# OSSILEDControllerNew.net
KiCad netlist of a schematic drawn in EAGLE
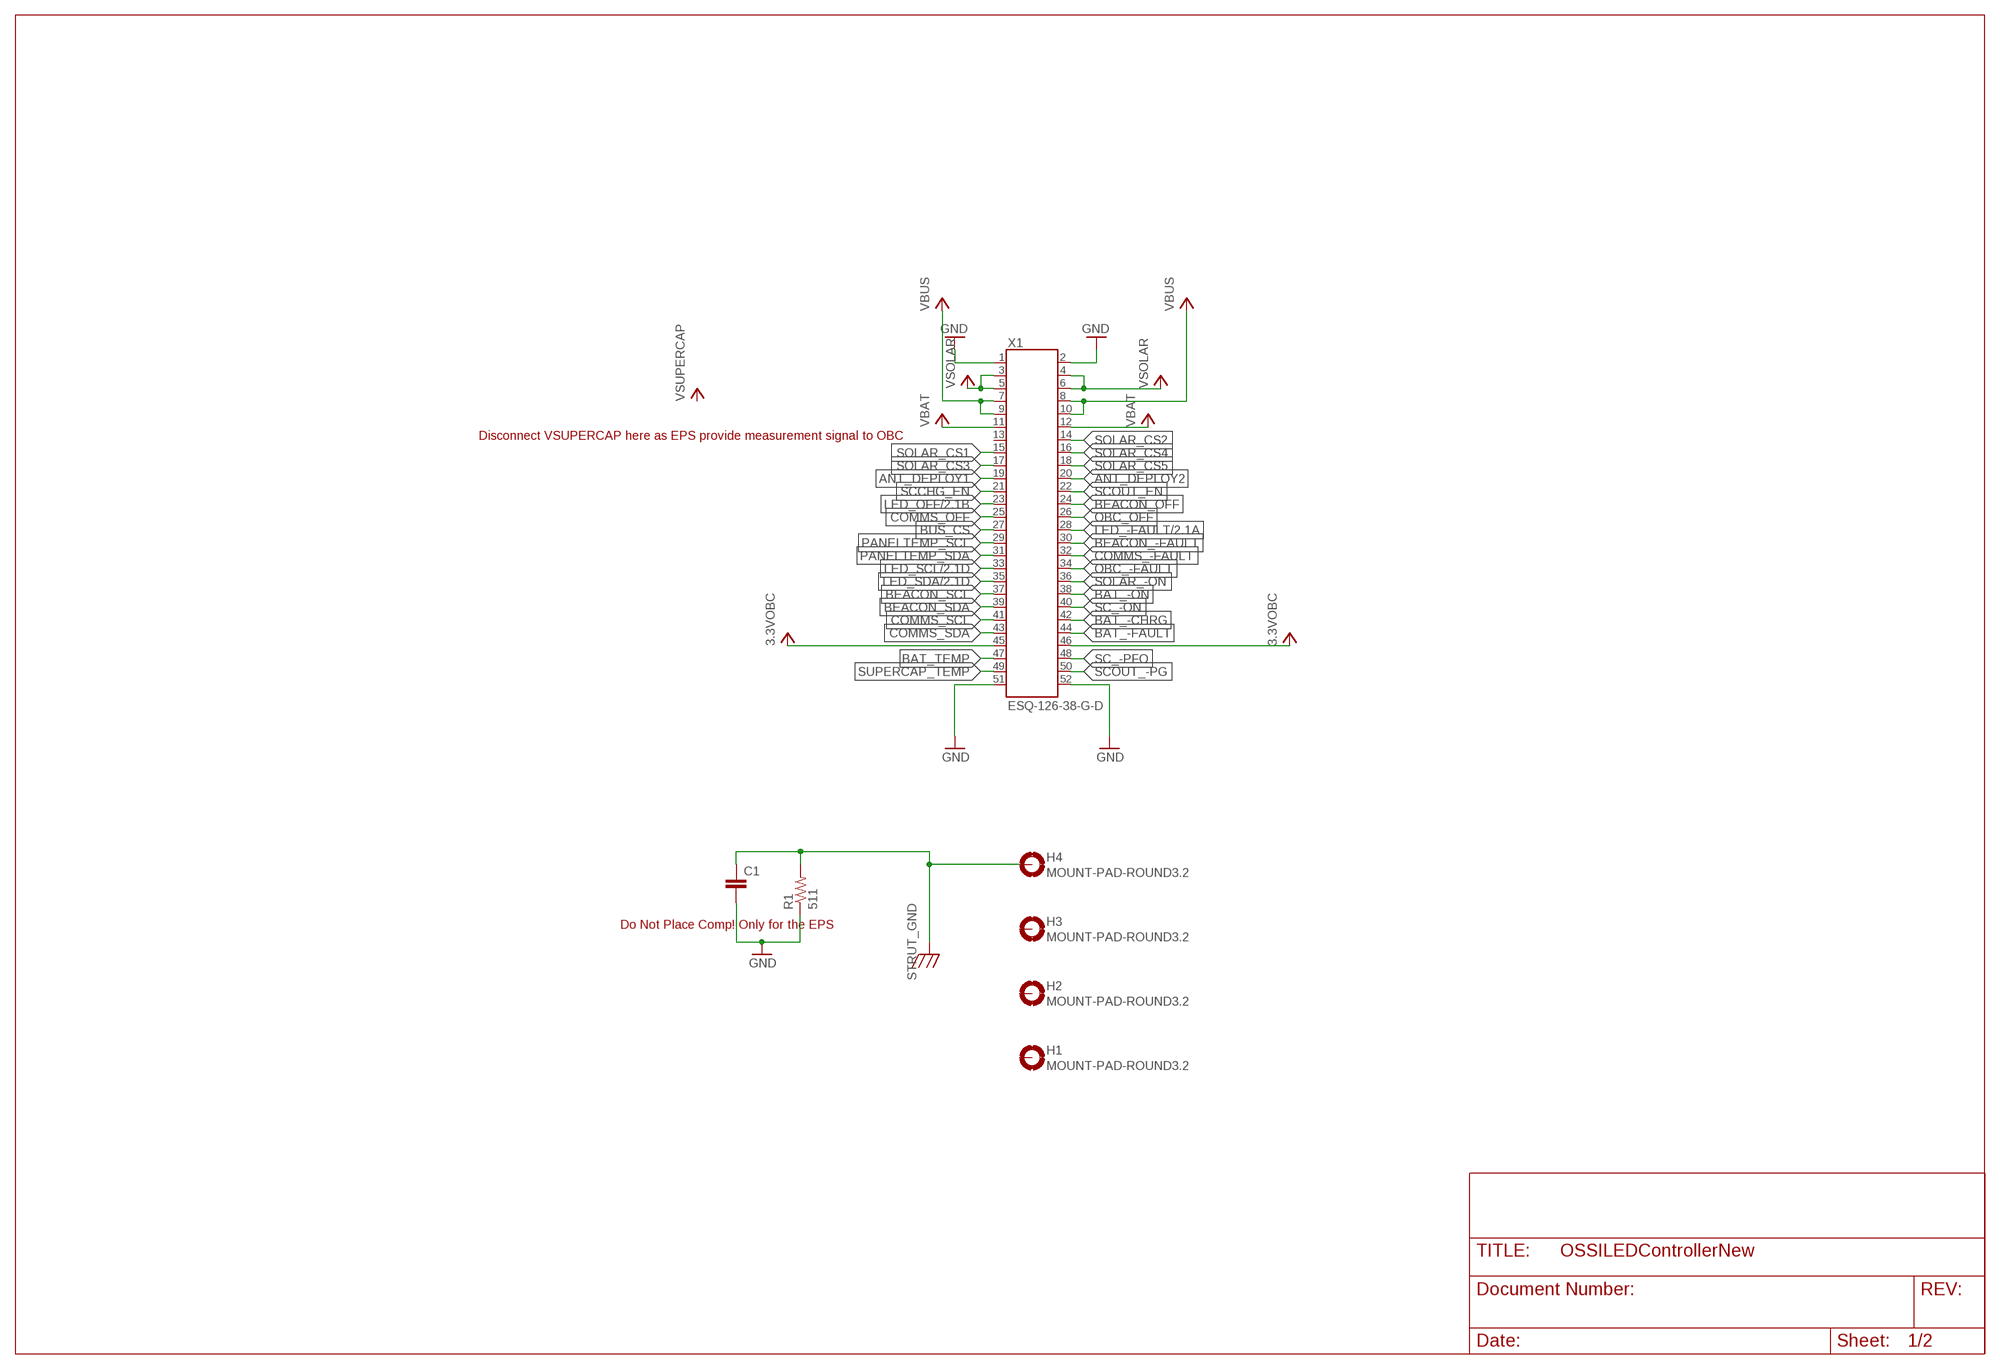
[diagram p0: schematic, sheet 1]
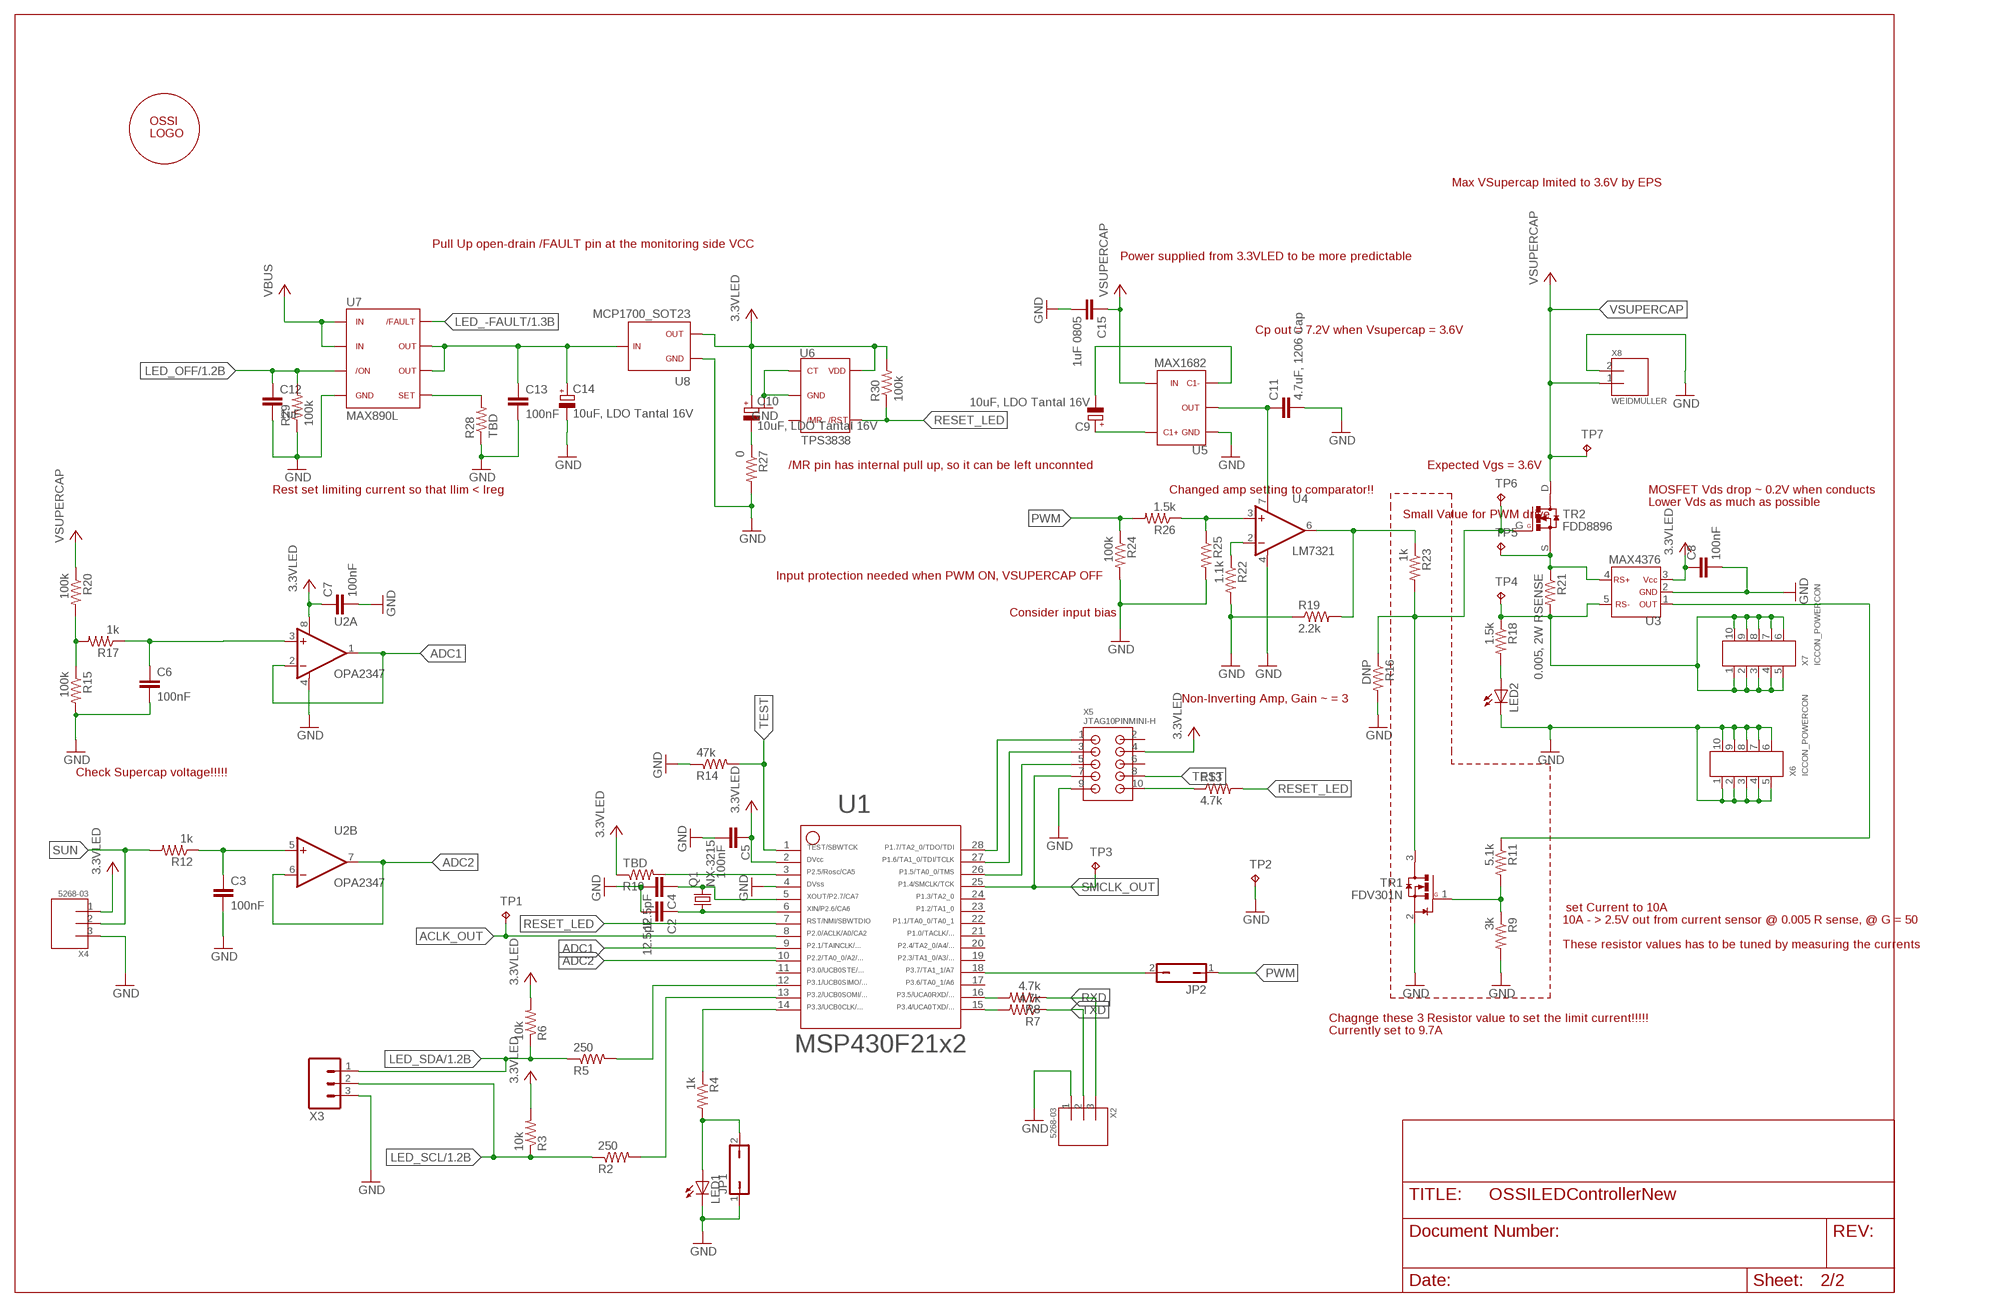
[diagram p1: schematic, sheet 2]

(export (version "E")
  (design (tool "Eeschema 10.0.6"))
  (components
    (comp (ref "C1")
      (value "C0805(2012)")
      (footprint "eagle-import:C0805(2012)")
      (libsource (lib "eagle-import") (part "C0805(2012)"))
    )
    (comp (ref "H1")
      (value "MOUNT-PAD-ROUND3.2")
      (footprint "eagle-import:3.2-PAD-ROUND")
      (libsource (lib "eagle-import") (part "MOUNT-PAD-ROUND3.2"))
    )
    (comp (ref "H2")
      (value "MOUNT-PAD-ROUND3.2")
      (footprint "eagle-import:3.2-PAD-ROUND")
      (libsource (lib "eagle-import") (part "MOUNT-PAD-ROUND3.2"))
    )
    (comp (ref "H3")
      (value "MOUNT-PAD-ROUND3.2")
      (footprint "eagle-import:3.2-PAD-ROUND")
      (libsource (lib "eagle-import") (part "MOUNT-PAD-ROUND3.2"))
    )
    (comp (ref "H4")
      (value "MOUNT-PAD-ROUND3.2")
      (footprint "eagle-import:3.2-PAD-ROUND")
      (libsource (lib "eagle-import") (part "MOUNT-PAD-ROUND3.2"))
    )
    (comp (ref "R1")
      (value "511")
      (footprint "eagle-import:WSL1206")
      (libsource (lib "eagle-import") (part "RWSL1206"))
    )
    (comp (ref "X1")
      (value "ESQ-126-38-G-D")
      (footprint "eagle-import:ESQ-126-XX-X-D")
      (libsource (lib "eagle-import") (part "ESQ-126-38-G-D"))
    )
    (comp (ref "C2")
      (value "12.5pF")
      (footprint "eagle-import:C0603(1608)")
      (libsource (lib "eagle-import") (part "C0603(1608)"))
    )
    (comp (ref "C3")
      (value "100nF")
      (footprint "eagle-import:C0603(1608)")
      (libsource (lib "eagle-import") (part "C0603(1608)"))
    )
    (comp (ref "C4")
      (value "12.5pF")
      (footprint "eagle-import:C0603(1608)")
      (libsource (lib "eagle-import") (part "C0603(1608)"))
    )
    (comp (ref "C5")
      (value "100nF")
      (footprint "eagle-import:C0603(1608)")
      (libsource (lib "eagle-import") (part "C0603(1608)"))
    )
    (comp (ref "C6")
      (value "100nF")
      (footprint "eagle-import:C0603(1608)")
      (libsource (lib "eagle-import") (part "C0603(1608)"))
    )
    (comp (ref "C7")
      (value "100nF")
      (footprint "eagle-import:C0603(1608)")
      (libsource (lib "eagle-import") (part "C0603(1608)"))
    )
    (comp (ref "C8")
      (value "100nF")
      (footprint "eagle-import:C0603(1608)")
      (libsource (lib "eagle-import") (part "C0603(1608)"))
    )
    (comp (ref "C9")
      (value "10uF, LDO Tantal 16V")
      (footprint "eagle-import:C1206(3216)-A")
      (libsource (lib "eagle-import") (part "C-TANTAL-A"))
    )
    (comp (ref "C10")
      (value "10uF, LDO Tantal 16V")
      (footprint "eagle-import:C1206(3216)-A")
      (libsource (lib "eagle-import") (part "C-TANTAL-A"))
    )
    (comp (ref "C11")
      (value "4.7uF, 1206 Cap")
      (footprint "eagle-import:C1206-GCM31")
      (libsource (lib "eagle-import") (part "C1206(3216)-GCM31"))
    )
    (comp (ref "C12")
      (value "1uF")
      (footprint "eagle-import:C0603(1608)")
      (libsource (lib "eagle-import") (part "C0603(1608)"))
    )
    (comp (ref "C13")
      (value "100nF")
      (footprint "eagle-import:C0603(1608)")
      (libsource (lib "eagle-import") (part "C0603(1608)"))
    )
    (comp (ref "C14")
      (value "10uF, LDO Tantal 16V")
      (footprint "eagle-import:C1206(3216)-A")
      (libsource (lib "eagle-import") (part "C-TANTAL-A"))
    )
    (comp (ref "C15")
      (value "1uF 0805")
      (footprint "eagle-import:C0805(2012)")
      (libsource (lib "eagle-import") (part "C0805(2012)"))
    )
    (comp (ref "JP1")
      (value "JP1Q")
      (footprint "eagle-import:JP1")
      (libsource (lib "eagle-import") (part "JP1Q"))
    )
    (comp (ref "JP2")
      (value "JP1Q")
      (footprint "eagle-import:JP1")
      (libsource (lib "eagle-import") (part "JP1Q"))
    )
    (comp (ref "LED1")
      (value "LED0603")
      (footprint "eagle-import:LED-0603")
      (libsource (lib "eagle-import") (part "LED0603"))
    )
    (comp (ref "LED2")
      (value "LEDCHIPLED_0603")
      (footprint "eagle-import:CHIPLED_0603")
      (libsource (lib "eagle-import") (part "LEDCHIPLED_0603"))
    )
    (comp (ref "Q1")
      (value "NX-3215")
      (footprint "eagle-import:NX-3215")
      (libsource (lib "eagle-import") (part "NX-3215"))
    )
    (comp (ref "R2")
      (value "250")
      (footprint "eagle-import:R0603(1608)")
      (libsource (lib "eagle-import") (part "R0603(1608)"))
    )
    (comp (ref "R3")
      (value "10k")
      (footprint "eagle-import:R0603(1608)")
      (libsource (lib "eagle-import") (part "R0603(1608)"))
    )
    (comp (ref "R4")
      (value "1k")
      (footprint "eagle-import:R0603(1608)")
      (libsource (lib "eagle-import") (part "R0603(1608)"))
    )
    (comp (ref "R5")
      (value "250")
      (footprint "eagle-import:R0603(1608)")
      (libsource (lib "eagle-import") (part "R0603(1608)"))
    )
    (comp (ref "R6")
      (value "10k")
      (footprint "eagle-import:R0603(1608)")
      (libsource (lib "eagle-import") (part "R0603(1608)"))
    )
    (comp (ref "R7")
      (value "4.7k")
      (footprint "eagle-import:R0603(1608)")
      (libsource (lib "eagle-import") (part "R0603(1608)"))
    )
    (comp (ref "R8")
      (value "4.7k")
      (footprint "eagle-import:R0603(1608)")
      (libsource (lib "eagle-import") (part "R0603(1608)"))
    )
    (comp (ref "R9")
      (value "3k")
      (footprint "eagle-import:R0603(1608)")
      (libsource (lib "eagle-import") (part "R0603(1608)"))
    )
    (comp (ref "R10")
      (value "TBD")
      (footprint "eagle-import:R0603(1608)")
      (libsource (lib "eagle-import") (part "R0603(1608)"))
    )
    (comp (ref "R11")
      (value "5.1k")
      (footprint "eagle-import:R0603(1608)")
      (libsource (lib "eagle-import") (part "R0603(1608)"))
    )
    (comp (ref "R12")
      (value "1k")
      (footprint "eagle-import:R0603(1608)")
      (libsource (lib "eagle-import") (part "R0603(1608)"))
    )
    (comp (ref "R13")
      (value "4.7k")
      (footprint "eagle-import:R0603(1608)")
      (libsource (lib "eagle-import") (part "R0603(1608)"))
    )
    (comp (ref "R14")
      (value "47k")
      (footprint "eagle-import:R0603(1608)")
      (libsource (lib "eagle-import") (part "R0603(1608)"))
    )
    (comp (ref "R15")
      (value "100k")
      (footprint "eagle-import:R0603(1608)")
      (libsource (lib "eagle-import") (part "R0603(1608)"))
    )
    (comp (ref "R16")
      (value "DNP")
      (footprint "eagle-import:R0603(1608)")
      (libsource (lib "eagle-import") (part "R0603(1608)"))
    )
    (comp (ref "R17")
      (value "1k")
      (footprint "eagle-import:R0603(1608)")
      (libsource (lib "eagle-import") (part "R0603(1608)"))
    )
    (comp (ref "R18")
      (value "1.5k")
      (footprint "eagle-import:R0603(1608)")
      (libsource (lib "eagle-import") (part "R0603(1608)"))
    )
    (comp (ref "R19")
      (value "2.2k")
      (footprint "eagle-import:R0603(1608)")
      (libsource (lib "eagle-import") (part "R0603(1608)"))
    )
    (comp (ref "R20")
      (value "100k")
      (footprint "eagle-import:R0603(1608)")
      (libsource (lib "eagle-import") (part "R0603(1608)"))
    )
    (comp (ref "R21")
      (value "0.005, 2W RSENSE")
      (footprint "eagle-import:R4527(12070)")
      (libsource (lib "eagle-import") (part "RWSR2"))
    )
    (comp (ref "R22")
      (value "1.1k")
      (footprint "eagle-import:R0603(1608)")
      (libsource (lib "eagle-import") (part "R0603(1608)"))
    )
    (comp (ref "R23")
      (value "1k")
      (footprint "eagle-import:R0603(1608)")
      (libsource (lib "eagle-import") (part "R0603(1608)"))
    )
    (comp (ref "R24")
      (value "100k")
      (footprint "eagle-import:R0603(1608)")
      (libsource (lib "eagle-import") (part "R0603(1608)"))
    )
    (comp (ref "R25")
      (value "R0603(1608)")
      (footprint "eagle-import:R0603(1608)")
      (libsource (lib "eagle-import") (part "R0603(1608)"))
    )
    (comp (ref "R26")
      (value "1.5k")
      (footprint "eagle-import:R0603(1608)")
      (libsource (lib "eagle-import") (part "R0603(1608)"))
    )
    (comp (ref "R27")
      (value "0")
      (footprint "eagle-import:R0603(1608)")
      (libsource (lib "eagle-import") (part "R0603(1608)"))
    )
    (comp (ref "R28")
      (value "TBD")
      (footprint "eagle-import:R0603(1608)")
      (libsource (lib "eagle-import") (part "R0603(1608)"))
    )
    (comp (ref "R29")
      (value "100k")
      (footprint "eagle-import:R0603(1608)")
      (libsource (lib "eagle-import") (part "R0603(1608)"))
    )
    (comp (ref "R30")
      (value "100k")
      (footprint "eagle-import:R0603(1608)")
      (libsource (lib "eagle-import") (part "R0603(1608)"))
    )
    (comp (ref "TP1")
      (value "TP")
      (footprint "eagle-import:TP-13")
      (libsource (lib "eagle-import") (part "TP"))
    )
    (comp (ref "TP2")
      (value "TP")
      (footprint "eagle-import:TP-13")
      (libsource (lib "eagle-import") (part "TP"))
    )
    (comp (ref "TP3")
      (value "TP")
      (footprint "eagle-import:TP-13")
      (libsource (lib "eagle-import") (part "TP"))
    )
    (comp (ref "TP4")
      (value "TP")
      (footprint "eagle-import:TP-13")
      (libsource (lib "eagle-import") (part "TP"))
    )
    (comp (ref "TP5")
      (value "TP")
      (footprint "eagle-import:TP-13")
      (libsource (lib "eagle-import") (part "TP"))
    )
    (comp (ref "TP6")
      (value "TP")
      (footprint "eagle-import:TP-13")
      (libsource (lib "eagle-import") (part "TP"))
    )
    (comp (ref "TP7")
      (value "TP")
      (footprint "eagle-import:TP-13")
      (libsource (lib "eagle-import") (part "TP"))
    )
    (comp (ref "TR1")
      (value "FDV301N")
      (footprint "eagle-import:SOT23")
      (libsource (lib "eagle-import") (part "FDV301N"))
    )
    (comp (ref "TR2")
      (value "FDD8896")
      (footprint "eagle-import:TO252")
      (libsource (lib "eagle-import") (part "FDD8896"))
    )
    (comp (ref "U$")
      (value "OSSILOGORECT")
      (footprint "eagle-import:OSSILOGORECT1005")
      (libsource (lib "eagle-import") (part "OSSILOGORECT"))
    )
    (comp (ref "U1")
      (value "MSP430F2132")
      (footprint "eagle-import:PW28")
      (libsource (lib "eagle-import") (part "MSP430F2132"))
    )
    (comp (ref "U2")
      (value "OPA2347")
      (footprint "eagle-import:SOT23-8DCN")
      (libsource (lib "eagle-import") (part "OPA2347"))
    )
    (comp (ref "U3")
      (value "MAX4376")
      (footprint "eagle-import:SOT23-5DBV")
      (libsource (lib "eagle-import") (part "MAX4376"))
    )
    (comp (ref "U4")
      (value "LM7321")
      (footprint "eagle-import:SO8")
      (libsource (lib "eagle-import") (part "LM7321"))
    )
    (comp (ref "U5")
      (value "MAX1682")
      (footprint "eagle-import:SOT23-5DBV")
      (libsource (lib "eagle-import") (part "MAX1682"))
    )
    (comp (ref "U6")
      (value "TPS3838")
      (footprint "eagle-import:SOT23-5DBV")
      (libsource (lib "eagle-import") (part "TPS3838"))
    )
    (comp (ref "U7")
      (value "MAX890L")
      (footprint "eagle-import:SO8")
      (libsource (lib "eagle-import") (part "MAX890L"))
    )
    (comp (ref "U8")
      (value "MCP1700_SOT23")
      (footprint "eagle-import:SOT23")
      (libsource (lib "eagle-import") (part "MCP1700_SOT23"))
    )
    (comp (ref "X2")
      (value "5268-03")
      (footprint "eagle-import:5268-03")
      (libsource (lib "eagle-import") (part "5268-03"))
    )
    (comp (ref "X3")
      (value "M03PTH")
      (footprint "eagle-import:1X03")
      (libsource (lib "eagle-import") (part "M03PTH"))
    )
    (comp (ref "X4")
      (value "5268-03")
      (footprint "eagle-import:5268-03")
      (libsource (lib "eagle-import") (part "5268-03"))
    )
    (comp (ref "X5")
      (value "JTAG10PINMINI-H")
      (footprint "eagle-import:M50-3200545")
      (libsource (lib "eagle-import") (part "JTAG10PINMINI-H"))
    )
    (comp (ref "X6")
      (value "ICCON_POWERCON")
      (footprint "eagle-import:ICCON6643220-1")
      (libsource (lib "eagle-import") (part "ICCON_POWERCON"))
    )
    (comp (ref "X7")
      (value "ICCON_POWERCON")
      (footprint "eagle-import:ICCON6643220-1")
      (libsource (lib "eagle-import") (part "ICCON_POWERCON"))
    )
    (comp (ref "X8")
      (value "WEIDMULLER")
      (footprint "eagle-import:WEIDMULLER1760490000")
      (libsource (lib "eagle-import") (part "WEIDMULLER"))
    )
  )
  (nets
    (net (code "1") (name "3.3VLED") (class "Default")
      (node (ref "C10") (pin "1") (pinfunction "+_1") (pintype "passive"))
      (node (ref "C5") (pin "1") (pinfunction "1_1") (pintype "passive"))
      (node (ref "C7") (pin "1") (pinfunction "1_1") (pintype "passive"))
      (node (ref "C8") (pin "1") (pinfunction "1_1") (pintype "passive"))
      (node (ref "R10") (pin "1") (pinfunction "1_1") (pintype "passive"))
      (node (ref "R3") (pin "2") (pinfunction "2_2") (pintype "passive"))
      (node (ref "R30") (pin "2") (pinfunction "2_2") (pintype "passive"))
      (node (ref "R6") (pin "2") (pinfunction "2_2") (pintype "passive"))
      (node (ref "U1") (pin "2") (pinfunction "2_2") (pintype "power_in"))
      (node (ref "U2") (pin "8") (pinfunction "V+_8") (pintype "power_in"))
      (node (ref "U3") (pin "3") (pinfunction "P$3_3") (pintype "power_in"))
      (node (ref "U6") (pin "5") (pinfunction "P$5_5") (pintype "power_in"))
      (node (ref "U8") (pin "2") (pinfunction "2_2") (pintype "power_in"))
      (node (ref "X4") (pin "1") (pinfunction "1_1") (pintype "bidirectional"))
      (node (ref "X5") (pin "4") (pinfunction "4_4") (pintype "bidirectional"))
    )
    (net (code "2") (name "3.3VOBC") (class "Default")
      (node (ref "X1") (pin "45") (pinfunction "45_45") (pintype "bidirectional"))
      (node (ref "X1") (pin "46") (pinfunction "46_46") (pintype "bidirectional"))
    )
    (net (code "3") (name "ACLK_OUT") (class "Default")
      (node (ref "TP1") (pin "TP") (pinfunction "TP_TP") (pintype "input"))
      (node (ref "U1") (pin "8") (pinfunction "8_8") (pintype "bidirectional"))
    )
    (net (code "4") (name "ADC1") (class "Default")
      (node (ref "U1") (pin "9") (pinfunction "9_9") (pintype "bidirectional"))
      (node (ref "U2") (pin "1") (pinfunction "OUT_1") (pintype "output"))
      (node (ref "U2") (pin "2") (pinfunction "-IN_2") (pintype "input"))
    )
    (net (code "5") (name "ADC2") (class "Default")
      (node (ref "U1") (pin "10") (pinfunction "10_10") (pintype "bidirectional"))
      (node (ref "U2") (pin "6") (pinfunction "-IN_6") (pintype "input"))
      (node (ref "U2") (pin "7") (pinfunction "OUT_7") (pintype "output"))
    )
    (net (code "6") (name "ANT_DEPLOY1") (class "Default")
      (node (ref "X1") (pin "19") (pinfunction "19_19") (pintype "bidirectional"))
    )
    (net (code "7") (name "ANT_DEPLOY2") (class "Default")
      (node (ref "X1") (pin "20") (pinfunction "20_20") (pintype "bidirectional"))
    )
    (net (code "8") (name "BAT_-CHRG") (class "Default")
      (node (ref "X1") (pin "42") (pinfunction "42_42") (pintype "bidirectional"))
    )
    (net (code "9") (name "BAT_-FAULT") (class "Default")
      (node (ref "X1") (pin "44") (pinfunction "44_44") (pintype "bidirectional"))
    )
    (net (code "10") (name "BAT_-ON") (class "Default")
      (node (ref "X1") (pin "38") (pinfunction "38_38") (pintype "bidirectional"))
    )
    (net (code "11") (name "BAT_TEMP") (class "Default")
      (node (ref "X1") (pin "47") (pinfunction "47_47") (pintype "bidirectional"))
    )
    (net (code "12") (name "BEACON_-FAULT") (class "Default")
      (node (ref "X1") (pin "30") (pinfunction "30_30") (pintype "bidirectional"))
    )
    (net (code "13") (name "BEACON_OFF") (class "Default")
      (node (ref "X1") (pin "24") (pinfunction "24_24") (pintype "bidirectional"))
    )
    (net (code "14") (name "BEACON_SCL") (class "Default")
      (node (ref "X1") (pin "37") (pinfunction "37_37") (pintype "bidirectional"))
    )
    (net (code "15") (name "BEACON_SDA") (class "Default")
      (node (ref "X1") (pin "39") (pinfunction "39_39") (pintype "bidirectional"))
    )
    (net (code "16") (name "BUS_CS") (class "Default")
      (node (ref "X1") (pin "27") (pinfunction "27_27") (pintype "bidirectional"))
    )
    (net (code "17") (name "COMMS_-FAULT") (class "Default")
      (node (ref "X1") (pin "32") (pinfunction "32_32") (pintype "bidirectional"))
    )
    (net (code "18") (name "COMMS_OFF") (class "Default")
      (node (ref "X1") (pin "25") (pinfunction "25_25") (pintype "bidirectional"))
    )
    (net (code "19") (name "COMMS_SCL") (class "Default")
      (node (ref "X1") (pin "41") (pinfunction "41_41") (pintype "bidirectional"))
    )
    (net (code "20") (name "COMMS_SDA") (class "Default")
      (node (ref "X1") (pin "43") (pinfunction "43_43") (pintype "bidirectional"))
    )
    (net (code "21") (name "GND") (class "Default")
      (node (ref "C1") (pin "2") (pinfunction "2_2") (pintype "passive"))
      (node (ref "C11") (pin "P$2") (pinfunction "2_P$2") (pintype "passive"))
      (node (ref "C12") (pin "2") (pinfunction "2_2") (pintype "passive"))
      (node (ref "C13") (pin "2") (pinfunction "2_2") (pintype "passive"))
      (node (ref "C14") (pin "2") (pinfunction "-_2") (pintype "passive"))
      (node (ref "C15") (pin "2") (pinfunction "2_2") (pintype "passive"))
      (node (ref "C2") (pin "2") (pinfunction "2_2") (pintype "passive"))
      (node (ref "C3") (pin "2") (pinfunction "2_2") (pintype "passive"))
      (node (ref "C4") (pin "2") (pinfunction "2_2") (pintype "passive"))
      (node (ref "C5") (pin "2") (pinfunction "2_2") (pintype "passive"))
      (node (ref "C6") (pin "2") (pinfunction "2_2") (pintype "passive"))
      (node (ref "C7") (pin "2") (pinfunction "2_2") (pintype "passive"))
      (node (ref "C8") (pin "2") (pinfunction "2_2") (pintype "passive"))
      (node (ref "JP1") (pin "1") (pinfunction "1_1") (pintype "passive"))
      (node (ref "LED1") (pin "C") (pinfunction "C_C") (pintype "passive"))
      (node (ref "LED2") (pin "C") (pinfunction "C_C") (pintype "passive"))
      (node (ref "R1") (pin "P$1") (pinfunction "1_P$1") (pintype "passive"))
      (node (ref "R14") (pin "1") (pinfunction "1_1") (pintype "passive"))
      (node (ref "R15") (pin "2") (pinfunction "2_2") (pintype "passive"))
      (node (ref "R16") (pin "2") (pinfunction "2_2") (pintype "passive"))
      (node (ref "R19") (pin "1") (pinfunction "1_1") (pintype "passive"))
      (node (ref "R22") (pin "2") (pinfunction "2_2") (pintype "passive"))
      (node (ref "R24") (pin "2") (pinfunction "2_2") (pintype "passive"))
      (node (ref "R25") (pin "2") (pinfunction "2_2") (pintype "passive"))
      (node (ref "R27") (pin "2") (pinfunction "2_2") (pintype "passive"))
      (node (ref "R28") (pin "1") (pinfunction "1_1") (pintype "passive"))
      (node (ref "R29") (pin "1") (pinfunction "1_1") (pintype "passive"))
      (node (ref "R9") (pin "2") (pinfunction "2_2") (pintype "passive"))
      (node (ref "TP2") (pin "TP") (pinfunction "TP_TP") (pintype "input"))
      (node (ref "TR1") (pin "2") (pinfunction "S_2") (pintype "bidirectional"))
      (node (ref "U1") (pin "4") (pinfunction "4_4") (pintype "power_in"))
      (node (ref "U2") (pin "4") (pinfunction "V-_4") (pintype "power_in"))
      (node (ref "U3") (pin "2") (pinfunction "P$2_2") (pintype "power_in"))
      (node (ref "U4") (pin "4") (pinfunction "V-_4") (pintype "power_in"))
      (node (ref "U5") (pin "1") (pinfunction "P$1_1") (pintype "power_in"))
      (node (ref "U6") (pin "1") (pinfunction "P$1_1") (pintype "bidirectional"))
      (node (ref "U6") (pin "2") (pinfunction "P$2_2") (pintype "power_in"))
      (node (ref "U7") (pin "4") (pinfunction "P$4_4") (pintype "power_in"))
      (node (ref "U8") (pin "1") (pinfunction "1_1") (pintype "power_in"))
      (node (ref "X1") (pin "1") (pinfunction "1_1") (pintype "bidirectional"))
      (node (ref "X1") (pin "2") (pinfunction "2_2") (pintype "bidirectional"))
      (node (ref "X1") (pin "51") (pinfunction "51_51") (pintype "bidirectional"))
      (node (ref "X1") (pin "52") (pinfunction "52_52") (pintype "bidirectional"))
      (node (ref "X2") (pin "1") (pinfunction "1_1") (pintype "bidirectional"))
      (node (ref "X3") (pin "3") (pinfunction "3_3") (pintype "passive"))
      (node (ref "X4") (pin "3") (pinfunction "3_3") (pintype "bidirectional"))
      (node (ref "X5") (pin "9") (pinfunction "9_9") (pintype "bidirectional"))
      (node (ref "X6") (pin "1") (pinfunction "P$1_1") (pintype "bidirectional"))
      (node (ref "X6") (pin "10") (pinfunction "P$10_10") (pintype "bidirectional"))
      (node (ref "X6") (pin "2") (pinfunction "P$2_2") (pintype "bidirectional"))
      (node (ref "X6") (pin "3") (pinfunction "P$3_3") (pintype "bidirectional"))
      (node (ref "X6") (pin "4") (pinfunction "P$4_4") (pintype "bidirectional"))
      (node (ref "X6") (pin "5") (pinfunction "P$5_5") (pintype "bidirectional"))
      (node (ref "X6") (pin "6") (pinfunction "P$6_6") (pintype "bidirectional"))
      (node (ref "X6") (pin "7") (pinfunction "P$7_7") (pintype "bidirectional"))
      (node (ref "X6") (pin "8") (pinfunction "P$8_8") (pintype "bidirectional"))
      (node (ref "X6") (pin "9") (pinfunction "P$9_9") (pintype "bidirectional"))
      (node (ref "X8") (pin "2") (pinfunction "2_2") (pintype "bidirectional"))
    )
    (net (code "22") (name "LED_-FAULT") (class "Default")
      (node (ref "U7") (pin "8") (pinfunction "P$8_8") (pintype "output"))
      (node (ref "X1") (pin "28") (pinfunction "28_28") (pintype "bidirectional"))
    )
    (net (code "23") (name "LED_OFF") (class "Default")
      (node (ref "C12") (pin "1") (pinfunction "1_1") (pintype "passive"))
      (node (ref "R29") (pin "2") (pinfunction "2_2") (pintype "passive"))
      (node (ref "U7") (pin "3") (pinfunction "P$3_3") (pintype "input"))
      (node (ref "X1") (pin "23") (pinfunction "23_23") (pintype "bidirectional"))
    )
    (net (code "24") (name "LED_SCL") (class "Default")
      (node (ref "R2") (pin "1") (pinfunction "1_1") (pintype "passive"))
      (node (ref "R3") (pin "1") (pinfunction "1_1") (pintype "passive"))
      (node (ref "X1") (pin "33") (pinfunction "33_33") (pintype "bidirectional"))
      (node (ref "X3") (pin "2") (pinfunction "2_2") (pintype "passive"))
    )
    (net (code "25") (name "LED_SDA") (class "Default")
      (node (ref "R5") (pin "1") (pinfunction "1_1") (pintype "passive"))
      (node (ref "R6") (pin "1") (pinfunction "1_1") (pintype "passive"))
      (node (ref "X1") (pin "35") (pinfunction "35_35") (pintype "bidirectional"))
      (node (ref "X3") (pin "1") (pinfunction "1_1") (pintype "passive"))
    )
    (net (code "26") (name "Net-(C2-Pad1)") (class "Default")
      (node (ref "C2") (pin "1") (pinfunction "1_1") (pintype "passive"))
      (node (ref "Q1") (pin "1") (pinfunction "1_1") (pintype "passive"))
      (node (ref "U1") (pin "6") (pinfunction "6_6") (pintype "bidirectional"))
    )
    (net (code "27") (name "Net-(C4-Pad1)") (class "Default")
      (node (ref "C4") (pin "1") (pinfunction "1_1") (pintype "passive"))
      (node (ref "Q1") (pin "2") (pinfunction "2_2") (pintype "passive"))
      (node (ref "U1") (pin "5") (pinfunction "5_5") (pintype "bidirectional"))
    )
    (net (code "28") (name "Net-(C9-+)") (class "Default")
      (node (ref "C9") (pin "1") (pinfunction "+_1") (pintype "passive"))
      (node (ref "U5") (pin "5") (pinfunction "P$5_5") (pintype "passive"))
    )
    (net (code "29") (name "Net-(C9--)") (class "Default")
      (node (ref "C9") (pin "2") (pinfunction "-_2") (pintype "passive"))
      (node (ref "U5") (pin "3") (pinfunction "P$3_3") (pintype "passive"))
    )
    (net (code "30") (name "Net-(C10--)") (class "Default")
      (node (ref "C10") (pin "2") (pinfunction "-_2") (pintype "passive"))
      (node (ref "R27") (pin "1") (pinfunction "1_1") (pintype "passive"))
    )
    (net (code "31") (name "Net-(C11-1)") (class "Default")
      (node (ref "C11") (pin "P$1") (pinfunction "1_P$1") (pintype "passive"))
      (node (ref "U4") (pin "7") (pinfunction "V+_7") (pintype "power_in"))
      (node (ref "U5") (pin "2") (pinfunction "P$2_2") (pintype "power_in"))
    )
    (net (code "32") (name "Net-(C14-+)") (class "Default")
      (node (ref "C13") (pin "1") (pinfunction "1_1") (pintype "passive"))
      (node (ref "C14") (pin "1") (pinfunction "+_1") (pintype "passive"))
      (node (ref "U7") (pin "6") (pinfunction "P$6_6") (pintype "output"))
      (node (ref "U7") (pin "7") (pinfunction "P$7_7") (pintype "output"))
      (node (ref "U8") (pin "3") (pinfunction "3_3") (pintype "power_in"))
    )
    (net (code "33") (name "Net-(JP1-Pad2)") (class "Default")
      (node (ref "JP1") (pin "2") (pinfunction "2_2") (pintype "passive"))
      (node (ref "LED1") (pin "A") (pinfunction "A_A") (pintype "passive"))
      (node (ref "R4") (pin "2") (pinfunction "2_2") (pintype "passive"))
    )
    (net (code "34") (name "Net-(JP2-Pad2)") (class "Default")
      (node (ref "JP2") (pin "2") (pinfunction "2_2") (pintype "passive"))
      (node (ref "U1") (pin "18") (pinfunction "18_18") (pintype "bidirectional"))
    )
    (net (code "35") (name "Net-(LED2-PadA)") (class "Default")
      (node (ref "LED2") (pin "A") (pinfunction "A_A") (pintype "passive"))
      (node (ref "R18") (pin "2") (pinfunction "2_2") (pintype "passive"))
    )
    (net (code "36") (name "Net-(R2-Pad2)") (class "Default")
      (node (ref "R2") (pin "2") (pinfunction "2_2") (pintype "passive"))
      (node (ref "U1") (pin "13") (pinfunction "13_13") (pintype "bidirectional"))
    )
    (net (code "37") (name "Net-(R4-Pad1)") (class "Default")
      (node (ref "R4") (pin "1") (pinfunction "1_1") (pintype "passive"))
      (node (ref "U1") (pin "14") (pinfunction "14_14") (pintype "bidirectional"))
    )
    (net (code "38") (name "Net-(R5-Pad2)") (class "Default")
      (node (ref "R5") (pin "2") (pinfunction "2_2") (pintype "passive"))
      (node (ref "U1") (pin "12") (pinfunction "12_12") (pintype "bidirectional"))
    )
    (net (code "39") (name "Net-(R7-Pad2)") (class "Default")
      (node (ref "R7") (pin "2") (pinfunction "2_2") (pintype "passive"))
      (node (ref "U1") (pin "15") (pinfunction "15_15") (pintype "bidirectional"))
    )
    (net (code "40") (name "Net-(R8-Pad2)") (class "Default")
      (node (ref "R8") (pin "2") (pinfunction "2_2") (pintype "passive"))
      (node (ref "U1") (pin "16") (pinfunction "16_16") (pintype "bidirectional"))
    )
    (net (code "41") (name "Net-(R10-Pad2)") (class "Default")
      (node (ref "R10") (pin "2") (pinfunction "2_2") (pintype "passive"))
      (node (ref "U1") (pin "3") (pinfunction "3_3") (pintype "bidirectional"))
    )
    (net (code "42") (name "Net-(R13-Pad1)") (class "Default")
      (node (ref "R13") (pin "1") (pinfunction "1_1") (pintype "passive"))
      (node (ref "X5") (pin "10") (pinfunction "10_10") (pintype "bidirectional"))
    )
    (net (code "43") (name "Net-(R15-Pad1)") (class "Default")
      (node (ref "R15") (pin "1") (pinfunction "1_1") (pintype "passive"))
      (node (ref "R17") (pin "2") (pinfunction "2_2") (pintype "passive"))
      (node (ref "R20") (pin "2") (pinfunction "2_2") (pintype "passive"))
    )
    (net (code "44") (name "Net-(R21-1)") (class "Default")
      (node (ref "R21") (pin "P$1") (pinfunction "1_P$1") (pintype "passive"))
      (node (ref "TP5") (pin "TP") (pinfunction "TP_TP") (pintype "input"))
      (node (ref "TR2") (pin "S") (pinfunction "S_S") (pintype "bidirectional"))
      (node (ref "U3") (pin "4") (pinfunction "P$4_4") (pintype "input"))
    )
    (net (code "45") (name "Net-(R21-2)") (class "Default")
      (node (ref "R18") (pin "1") (pinfunction "1_1") (pintype "passive"))
      (node (ref "R21") (pin "P$2") (pinfunction "2_P$2") (pintype "passive"))
      (node (ref "TP4") (pin "TP") (pinfunction "TP_TP") (pintype "input"))
      (node (ref "U3") (pin "5") (pinfunction "P$5_5") (pintype "input"))
      (node (ref "X7") (pin "1") (pinfunction "P$1_1") (pintype "bidirectional"))
      (node (ref "X7") (pin "10") (pinfunction "P$10_10") (pintype "bidirectional"))
      (node (ref "X7") (pin "2") (pinfunction "P$2_2") (pintype "bidirectional"))
      (node (ref "X7") (pin "3") (pinfunction "P$3_3") (pintype "bidirectional"))
      (node (ref "X7") (pin "4") (pinfunction "P$4_4") (pintype "bidirectional"))
      (node (ref "X7") (pin "5") (pinfunction "P$5_5") (pintype "bidirectional"))
      (node (ref "X7") (pin "6") (pinfunction "P$6_6") (pintype "bidirectional"))
      (node (ref "X7") (pin "7") (pinfunction "P$7_7") (pintype "bidirectional"))
      (node (ref "X7") (pin "8") (pinfunction "P$8_8") (pintype "bidirectional"))
      (node (ref "X7") (pin "9") (pinfunction "P$9_9") (pintype "bidirectional"))
    )
    (net (code "46") (name "Net-(TR1-D)") (class "Default")
      (node (ref "R16") (pin "1") (pinfunction "1_1") (pintype "passive"))
      (node (ref "R23") (pin "2") (pinfunction "2_2") (pintype "passive"))
      (node (ref "TP6") (pin "TP") (pinfunction "TP_TP") (pintype "input"))
      (node (ref "TR1") (pin "3") (pinfunction "D_3") (pintype "bidirectional"))
      (node (ref "TR2") (pin "G") (pinfunction "G_G") (pintype "bidirectional"))
    )
    (net (code "47") (name "Net-(TR1-G)") (class "Default")
      (node (ref "R11") (pin "2") (pinfunction "2_2") (pintype "passive"))
      (node (ref "R9") (pin "1") (pinfunction "1_1") (pintype "passive"))
      (node (ref "TR1") (pin "1") (pinfunction "G_1") (pintype "bidirectional"))
    )
    (net (code "48") (name "Net-(U1-Pad26)") (class "Default")
      (node (ref "U1") (pin "26") (pinfunction "26_26") (pintype "bidirectional"))
      (node (ref "X5") (pin "5") (pinfunction "5_5") (pintype "bidirectional"))
    )
    (net (code "49") (name "Net-(U1-Pad27)") (class "Default")
      (node (ref "U1") (pin "27") (pinfunction "27_27") (pintype "bidirectional"))
      (node (ref "X5") (pin "3") (pinfunction "3_3") (pintype "bidirectional"))
    )
    (net (code "50") (name "Net-(U1-Pad28)") (class "Default")
      (node (ref "U1") (pin "28") (pinfunction "28_28") (pintype "bidirectional"))
      (node (ref "X5") (pin "1") (pinfunction "1_1") (pintype "bidirectional"))
    )
    (net (code "51") (name "Net-(U2A-+IN)") (class "Default")
      (node (ref "C6") (pin "1") (pinfunction "1_1") (pintype "passive"))
      (node (ref "R17") (pin "1") (pinfunction "1_1") (pintype "passive"))
      (node (ref "U2") (pin "3") (pinfunction "+IN_3") (pintype "input"))
    )
    (net (code "52") (name "Net-(U2B-+IN)") (class "Default")
      (node (ref "C3") (pin "1") (pinfunction "1_1") (pintype "passive"))
      (node (ref "R12") (pin "1") (pinfunction "1_1") (pintype "passive"))
      (node (ref "U2") (pin "5") (pinfunction "+IN_5") (pintype "input"))
    )
    (net (code "53") (name "Net-(U3-P$1)") (class "Default")
      (node (ref "R11") (pin "1") (pinfunction "1_1") (pintype "passive"))
      (node (ref "U3") (pin "1") (pinfunction "P$1_1") (pintype "output"))
    )
    (net (code "54") (name "Net-(U4-+IN)") (class "Default")
      (node (ref "R25") (pin "1") (pinfunction "1_1") (pintype "passive"))
      (node (ref "R26") (pin "1") (pinfunction "1_1") (pintype "passive"))
      (node (ref "U4") (pin "3") (pinfunction "+IN_3") (pintype "input"))
    )
    (net (code "55") (name "Net-(U4--IN)") (class "Default")
      (node (ref "R22") (pin "1") (pinfunction "1_1") (pintype "passive"))
      (node (ref "U4") (pin "2") (pinfunction "-IN_2") (pintype "input"))
    )
    (net (code "56") (name "Net-(U4-OUT)") (class "Default")
      (node (ref "R19") (pin "2") (pinfunction "2_2") (pintype "passive"))
      (node (ref "R23") (pin "1") (pinfunction "1_1") (pintype "passive"))
      (node (ref "U4") (pin "6") (pinfunction "OUT_6") (pintype "output"))
    )
    (net (code "57") (name "Net-(U7-P$5)") (class "Default")
      (node (ref "R28") (pin "2") (pinfunction "2_2") (pintype "passive"))
      (node (ref "U7") (pin "5") (pinfunction "P$5_5") (pintype "passive"))
    )
    (net (code "58") (name "OBC_-FAULT") (class "Default")
      (node (ref "X1") (pin "34") (pinfunction "34_34") (pintype "bidirectional"))
    )
    (net (code "59") (name "OBC_OFF") (class "Default")
      (node (ref "X1") (pin "26") (pinfunction "26_26") (pintype "bidirectional"))
    )
    (net (code "60") (name "PANELTEMP_SCL") (class "Default")
      (node (ref "X1") (pin "29") (pinfunction "29_29") (pintype "bidirectional"))
    )
    (net (code "61") (name "PANELTEMP_SDA") (class "Default")
      (node (ref "X1") (pin "31") (pinfunction "31_31") (pintype "bidirectional"))
    )
    (net (code "62") (name "PWM") (class "Default")
      (node (ref "JP2") (pin "1") (pinfunction "1_1") (pintype "passive"))
      (node (ref "R24") (pin "1") (pinfunction "1_1") (pintype "passive"))
      (node (ref "R26") (pin "2") (pinfunction "2_2") (pintype "passive"))
    )
    (net (code "63") (name "RESET_LED") (class "Default")
      (node (ref "R13") (pin "2") (pinfunction "2_2") (pintype "passive"))
      (node (ref "R30") (pin "1") (pinfunction "1_1") (pintype "passive"))
      (node (ref "U1") (pin "7") (pinfunction "7_7") (pintype "input"))
      (node (ref "U6") (pin "4") (pinfunction "P$4_4") (pintype "output"))
    )
    (net (code "64") (name "RXD") (class "Default")
      (node (ref "R8") (pin "1") (pinfunction "1_1") (pintype "passive"))
      (node (ref "X2") (pin "3") (pinfunction "3_3") (pintype "bidirectional"))
    )
    (net (code "65") (name "SCCHG_EN") (class "Default")
      (node (ref "X1") (pin "21") (pinfunction "21_21") (pintype "bidirectional"))
    )
    (net (code "66") (name "SCOUT_-PG") (class "Default")
      (node (ref "X1") (pin "50") (pinfunction "50_50") (pintype "bidirectional"))
    )
    (net (code "67") (name "SCOUT_EN") (class "Default")
      (node (ref "X1") (pin "22") (pinfunction "22_22") (pintype "bidirectional"))
    )
    (net (code "68") (name "SC_-ON") (class "Default")
      (node (ref "X1") (pin "40") (pinfunction "40_40") (pintype "bidirectional"))
    )
    (net (code "69") (name "SC_-PFO") (class "Default")
      (node (ref "X1") (pin "48") (pinfunction "48_48") (pintype "bidirectional"))
    )
    (net (code "70") (name "SMCLK_OUT") (class "Default")
      (node (ref "TP3") (pin "TP") (pinfunction "TP_TP") (pintype "input"))
      (node (ref "U1") (pin "25") (pinfunction "25_25") (pintype "bidirectional"))
      (node (ref "X5") (pin "7") (pinfunction "7_7") (pintype "bidirectional"))
    )
    (net (code "71") (name "SOLAR_-ON") (class "Default")
      (node (ref "X1") (pin "36") (pinfunction "36_36") (pintype "bidirectional"))
    )
    (net (code "72") (name "SOLAR_CS1") (class "Default")
      (node (ref "X1") (pin "15") (pinfunction "15_15") (pintype "bidirectional"))
    )
    (net (code "73") (name "SOLAR_CS2") (class "Default")
      (node (ref "X1") (pin "14") (pinfunction "14_14") (pintype "bidirectional"))
    )
    (net (code "74") (name "SOLAR_CS3") (class "Default")
      (node (ref "X1") (pin "17") (pinfunction "17_17") (pintype "bidirectional"))
    )
    (net (code "75") (name "SOLAR_CS4") (class "Default")
      (node (ref "X1") (pin "16") (pinfunction "16_16") (pintype "bidirectional"))
    )
    (net (code "76") (name "SOLAR_CS5") (class "Default")
      (node (ref "X1") (pin "18") (pinfunction "18_18") (pintype "bidirectional"))
    )
    (net (code "77") (name "STRUT_GND") (class "Default")
      (node (ref "C1") (pin "1") (pinfunction "1_1") (pintype "passive"))
      (node (ref "H4") (pin "B3,2") (pinfunction "MOUNT_B3,2") (pintype "passive"))
      (node (ref "R1") (pin "P$2") (pinfunction "2_P$2") (pintype "passive"))
    )
    (net (code "78") (name "SUN") (class "Default")
      (node (ref "R12") (pin "2") (pinfunction "2_2") (pintype "passive"))
      (node (ref "X4") (pin "2") (pinfunction "2_2") (pintype "bidirectional"))
    )
    (net (code "79") (name "SUPERCAP_TEMP") (class "Default")
      (node (ref "X1") (pin "49") (pinfunction "49_49") (pintype "bidirectional"))
    )
    (net (code "80") (name "TEST") (class "Default")
      (node (ref "R14") (pin "2") (pinfunction "2_2") (pintype "passive"))
      (node (ref "U1") (pin "1") (pinfunction "1_1") (pintype "input"))
      (node (ref "X5") (pin "8") (pinfunction "8_8") (pintype "bidirectional"))
    )
    (net (code "81") (name "TXD") (class "Default")
      (node (ref "R7") (pin "1") (pinfunction "1_1") (pintype "passive"))
      (node (ref "X2") (pin "2") (pinfunction "2_2") (pintype "bidirectional"))
    )
    (net (code "82") (name "VBAT") (class "Default")
      (node (ref "X1") (pin "11") (pinfunction "11_11") (pintype "bidirectional"))
      (node (ref "X1") (pin "12") (pinfunction "12_12") (pintype "bidirectional"))
    )
    (net (code "83") (name "VBUS") (class "Default")
      (node (ref "U7") (pin "1") (pinfunction "P$1_1") (pintype "input"))
      (node (ref "U7") (pin "2") (pinfunction "P$2_2") (pintype "input"))
      (node (ref "X1") (pin "10") (pinfunction "10_10") (pintype "bidirectional"))
      (node (ref "X1") (pin "7") (pinfunction "7_7") (pintype "bidirectional"))
      (node (ref "X1") (pin "8") (pinfunction "8_8") (pintype "bidirectional"))
      (node (ref "X1") (pin "9") (pinfunction "9_9") (pintype "bidirectional"))
    )
    (net (code "84") (name "VSOLAR") (class "Default")
      (node (ref "X1") (pin "3") (pinfunction "3_3") (pintype "bidirectional"))
      (node (ref "X1") (pin "4") (pinfunction "4_4") (pintype "bidirectional"))
      (node (ref "X1") (pin "5") (pinfunction "5_5") (pintype "bidirectional"))
      (node (ref "X1") (pin "6") (pinfunction "6_6") (pintype "bidirectional"))
    )
    (net (code "85") (name "VSUPERCAP") (class "Default")
      (node (ref "C15") (pin "1") (pinfunction "1_1") (pintype "passive"))
      (node (ref "R20") (pin "1") (pinfunction "1_1") (pintype "passive"))
      (node (ref "TP7") (pin "TP") (pinfunction "TP_TP") (pintype "input"))
      (node (ref "TR2") (pin "D") (pinfunction "D_D") (pintype "bidirectional"))
      (node (ref "U5") (pin "4") (pinfunction "P$4_4") (pintype "power_in"))
      (node (ref "X8") (pin "1") (pinfunction "1_1") (pintype "bidirectional"))
    )
    (net (code "86") (name "unconnected-(H1-MOUNT-PadB3,2)") (class "Default")
      (node (ref "H1") (pin "B3,2") (pinfunction "MOUNT_B3,2") (pintype "passive"))
    )
    (net (code "87") (name "unconnected-(H2-MOUNT-PadB3,2)") (class "Default")
      (node (ref "H2") (pin "B3,2") (pinfunction "MOUNT_B3,2") (pintype "passive"))
    )
    (net (code "88") (name "unconnected-(H3-MOUNT-PadB3,2)") (class "Default")
      (node (ref "H3") (pin "B3,2") (pinfunction "MOUNT_B3,2") (pintype "passive"))
    )
    (net (code "89") (name "unconnected-(U1-Pad11)") (class "Default")
      (node (ref "U1") (pin "11") (pinfunction "11_11") (pintype "bidirectional"))
    )
    (net (code "90") (name "unconnected-(U1-Pad17)") (class "Default")
      (node (ref "U1") (pin "17") (pinfunction "17_17") (pintype "bidirectional"))
    )
    (net (code "91") (name "unconnected-(U1-Pad19)") (class "Default")
      (node (ref "U1") (pin "19") (pinfunction "19_19") (pintype "bidirectional"))
    )
    (net (code "92") (name "unconnected-(U1-Pad20)") (class "Default")
      (node (ref "U1") (pin "20") (pinfunction "20_20") (pintype "bidirectional"))
    )
    (net (code "93") (name "unconnected-(U1-Pad21)") (class "Default")
      (node (ref "U1") (pin "21") (pinfunction "21_21") (pintype "bidirectional"))
    )
    (net (code "94") (name "unconnected-(U1-Pad22)") (class "Default")
      (node (ref "U1") (pin "22") (pinfunction "22_22") (pintype "bidirectional"))
    )
    (net (code "95") (name "unconnected-(U1-Pad23)") (class "Default")
      (node (ref "U1") (pin "23") (pinfunction "23_23") (pintype "bidirectional"))
    )
    (net (code "96") (name "unconnected-(U1-Pad24)") (class "Default")
      (node (ref "U1") (pin "24") (pinfunction "24_24") (pintype "bidirectional"))
    )
    (net (code "97") (name "unconnected-(U6-P$3-Pad3)") (class "Default")
      (node (ref "U6") (pin "3") (pinfunction "P$3_3") (pintype "input"))
    )
    (net (code "98") (name "unconnected-(X1-Pad13)") (class "Default")
      (node (ref "X1") (pin "13") (pinfunction "13_13") (pintype "bidirectional"))
    )
    (net (code "99") (name "unconnected-(X5-Pad2)") (class "Default")
      (node (ref "X5") (pin "2") (pinfunction "2_2") (pintype "bidirectional"))
    )
    (net (code "100") (name "unconnected-(X5-Pad6)") (class "Default")
      (node (ref "X5") (pin "6") (pinfunction "6_6") (pintype "bidirectional"))
    )
  )
)
